# 4port_driver.net
KiCad netlist of a schematic drawn in EAGLE
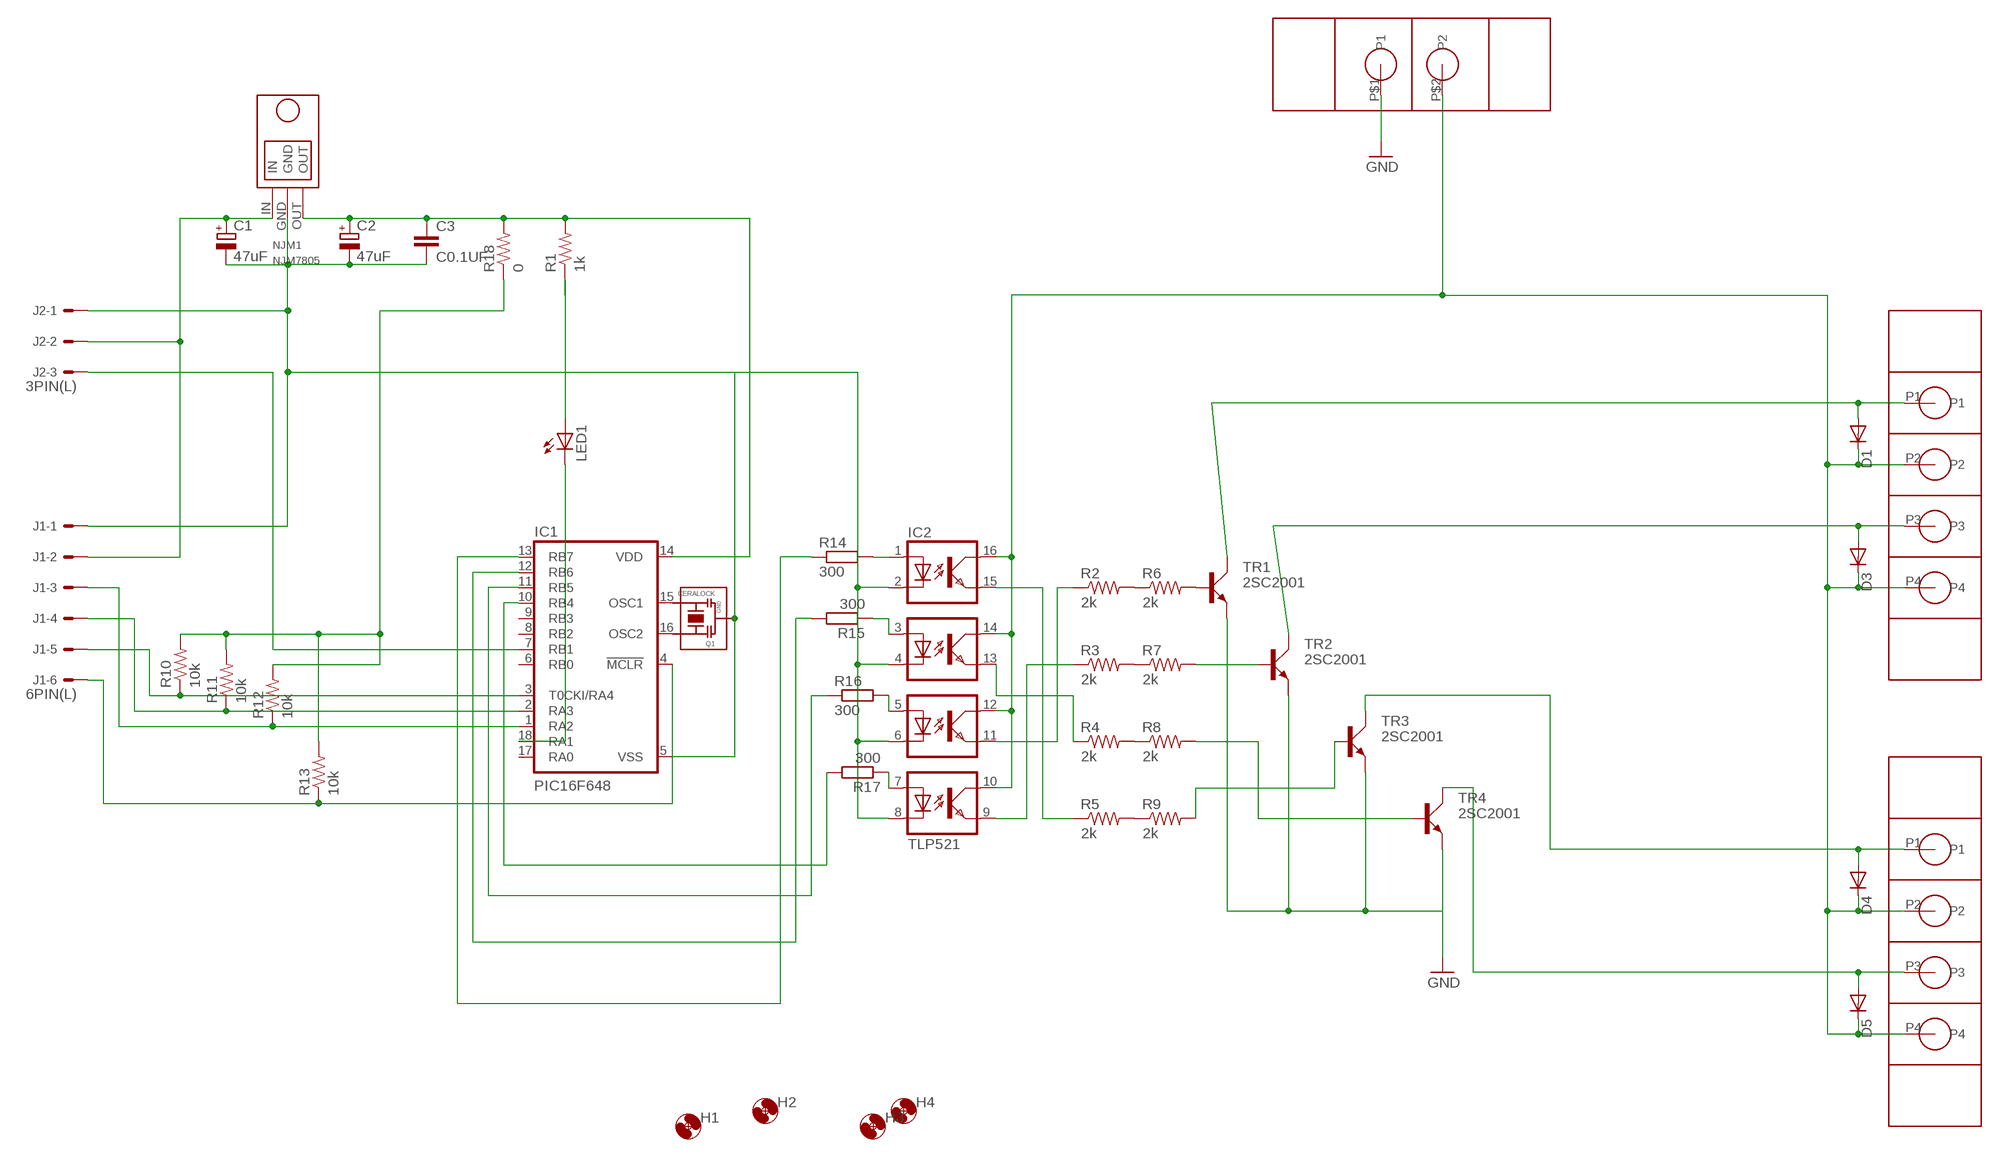
[diagram p0: schematic, sheet 1]

(export (version "E")
  (design (tool "Eeschema 10.0.6"))
  (components
    (comp (ref "C1")
      (value "47uF")
      (footprint "eagle-import:C-6MM")
      (libsource (lib "eagle-import") (part "C-ELEC"))
    )
    (comp (ref "C2")
      (value "47uF")
      (footprint "eagle-import:C-6MM")
      (libsource (lib "eagle-import") (part "C-ELEC"))
    )
    (comp (ref "C3")
      (value "C0.1UF")
      (footprint "eagle-import:C0.1UF")
      (libsource (lib "eagle-import") (part "C0.1UF"))
    )
    (comp (ref "D1")
      (value "DIODE7.5")
      (footprint "eagle-import:DIODE7.5")
      (libsource (lib "eagle-import") (part "DIODE7.5"))
    )
    (comp (ref "D3")
      (value "DIODE7.5")
      (footprint "eagle-import:DIODE7.5")
      (libsource (lib "eagle-import") (part "DIODE7.5"))
    )
    (comp (ref "D4")
      (value "DIODE7.5")
      (footprint "eagle-import:DIODE7.5")
      (libsource (lib "eagle-import") (part "DIODE7.5"))
    )
    (comp (ref "D5")
      (value "DIODE7.5")
      (footprint "eagle-import:DIODE7.5")
      (libsource (lib "eagle-import") (part "DIODE7.5"))
    )
    (comp (ref "H1")
      (value "HOLE3.3M3BOLT")
      (footprint "eagle-import:HOLE3.3")
      (libsource (lib "eagle-import") (part "HOLE3.3M3BOLT"))
    )
    (comp (ref "H2")
      (value "HOLE3.3M3BOLT")
      (footprint "eagle-import:HOLE3.3")
      (libsource (lib "eagle-import") (part "HOLE3.3M3BOLT"))
    )
    (comp (ref "H3")
      (value "HOLE3.3M3BOLT")
      (footprint "eagle-import:HOLE3.3")
      (libsource (lib "eagle-import") (part "HOLE3.3M3BOLT"))
    )
    (comp (ref "H4")
      (value "HOLE3.3M3BOLT")
      (footprint "eagle-import:HOLE3.3")
      (libsource (lib "eagle-import") (part "HOLE3.3M3BOLT"))
    )
    (comp (ref "IC1")
      (value "PIC16F648")
      (footprint "eagle-import:DIL18")
      (libsource (lib "eagle-import") (part "PIC16F648"))
    )
    (comp (ref "IC2")
      (value "TLP521")
      (footprint "eagle-import:DIL16")
      (libsource (lib "eagle-import") (part "TLP521"))
    )
    (comp (ref "J1")
      (value "6PIN(L)")
      (footprint "eagle-import:6PL")
      (libsource (lib "eagle-import") (part "6PIN(L)"))
    )
    (comp (ref "J2")
      (value "3PIN(L)")
      (footprint "eagle-import:3PL")
      (libsource (lib "eagle-import") (part "3PIN(L)"))
    )
    (comp (ref "LED1")
      (value "LED")
      (footprint "eagle-import:LED5MM")
      (libsource (lib "eagle-import") (part "LED"))
    )
    (comp (ref "NJM1")
      (value "NJM7805")
      (footprint "eagle-import:NJM7805")
      (libsource (lib "eagle-import") (part "NJM7805"))
    )
    (comp (ref "Q1")
      (value "CERALOCK")
      (footprint "eagle-import:CERALOCK")
      (libsource (lib "eagle-import") (part "CERALOCK"))
    )
    (comp (ref "R1")
      (value "1k")
      (footprint "eagle-import:0207_10")
      (libsource (lib "eagle-import") (part "R-"))
    )
    (comp (ref "R2")
      (value "2k")
      (footprint "eagle-import:0207_10")
      (libsource (lib "eagle-import") (part "R-"))
    )
    (comp (ref "R3")
      (value "2k")
      (footprint "eagle-import:0207_10")
      (libsource (lib "eagle-import") (part "R-"))
    )
    (comp (ref "R4")
      (value "2k")
      (footprint "eagle-import:0207_10")
      (libsource (lib "eagle-import") (part "R-"))
    )
    (comp (ref "R5")
      (value "2k")
      (footprint "eagle-import:0207_10")
      (libsource (lib "eagle-import") (part "R-"))
    )
    (comp (ref "R6")
      (value "2k")
      (footprint "eagle-import:0207_10")
      (libsource (lib "eagle-import") (part "R-"))
    )
    (comp (ref "R7")
      (value "2k")
      (footprint "eagle-import:0207_10")
      (libsource (lib "eagle-import") (part "R-"))
    )
    (comp (ref "R8")
      (value "2k")
      (footprint "eagle-import:0207_10")
      (libsource (lib "eagle-import") (part "R-"))
    )
    (comp (ref "R9")
      (value "2k")
      (footprint "eagle-import:0207_10")
      (libsource (lib "eagle-import") (part "R-"))
    )
    (comp (ref "R10")
      (value "10k")
      (footprint "eagle-import:0207_10")
      (libsource (lib "eagle-import") (part "R-"))
    )
    (comp (ref "R11")
      (value "10k")
      (footprint "eagle-import:0207_10")
      (libsource (lib "eagle-import") (part "R-"))
    )
    (comp (ref "R12")
      (value "10k")
      (footprint "eagle-import:0207_10")
      (libsource (lib "eagle-import") (part "R-"))
    )
    (comp (ref "R13")
      (value "10k")
      (footprint "eagle-import:0207_10")
      (libsource (lib "eagle-import") (part "R-"))
    )
    (comp (ref "R14")
      (value "300")
      (footprint "eagle-import:R0207V")
      (libsource (lib "eagle-import") (part "R-EU2R0207V"))
    )
    (comp (ref "R15")
      (value "300")
      (footprint "eagle-import:R0207V")
      (libsource (lib "eagle-import") (part "R-EU2R0207V"))
    )
    (comp (ref "R16")
      (value "300")
      (footprint "eagle-import:R0207V")
      (libsource (lib "eagle-import") (part "R-EU2R0207V"))
    )
    (comp (ref "R17")
      (value "300")
      (footprint "eagle-import:R0207V")
      (libsource (lib "eagle-import") (part "R-EU2R0207V"))
    )
    (comp (ref "R18")
      (value "0")
      (footprint "eagle-import:0207_10")
      (libsource (lib "eagle-import") (part "R-"))
    )
    (comp (ref "TR1")
      (value "2SC2001")
      (footprint "eagle-import:TO92BCE")
      (libsource (lib "eagle-import") (part "2SC2001"))
    )
    (comp (ref "TR2")
      (value "2SC2001")
      (footprint "eagle-import:TO92BCE")
      (libsource (lib "eagle-import") (part "2SC2001"))
    )
    (comp (ref "TR3")
      (value "2SC2001")
      (footprint "eagle-import:TO92BCE")
      (libsource (lib "eagle-import") (part "2SC2001"))
    )
    (comp (ref "TR4")
      (value "2SC2001")
      (footprint "eagle-import:TO92BCE")
      (libsource (lib "eagle-import") (part "2SC2001"))
    )
    (comp (ref "U$1")
      (value "BP341L_1")
      (footprint "eagle-import:BP341L")
      (libsource (lib "eagle-import") (part "BP341L_1"))
    )
    (comp (ref "U$2")
      (value "BP341L")
      (footprint "eagle-import:BP341L")
      (libsource (lib "eagle-import") (part "BP341L"))
    )
    (comp (ref "U$3")
      (value "BP341L")
      (footprint "eagle-import:BP341L")
      (libsource (lib "eagle-import") (part "BP341L"))
    )
  )
  (nets
    (net (code "1") (name "GND") (class "Default")
      (node (ref "TR1") (pin "E") (pinfunction "E_E") (pintype "passive"))
      (node (ref "TR2") (pin "E") (pinfunction "E_E") (pintype "passive"))
      (node (ref "TR3") (pin "E") (pinfunction "E_E") (pintype "passive"))
      (node (ref "TR4") (pin "E") (pinfunction "E_E") (pintype "passive"))
      (node (ref "U$1") (pin "P$1") (pinfunction "P1_P$1") (pintype "bidirectional"))
    )
    (net (code "2") (name "Net-(D1-A)") (class "Default")
      (node (ref "D1") (pin "PA") (pinfunction "A_PA") (pintype "passive"))
      (node (ref "TR1") (pin "C") (pinfunction "C_C") (pintype "passive"))
      (node (ref "U$2") (pin "P1") (pinfunction "P1_P1") (pintype "bidirectional"))
    )
    (net (code "3") (name "Net-(D1-C)") (class "Default")
      (node (ref "D1") (pin "PK") (pinfunction "C_PK") (pintype "passive"))
      (node (ref "D3") (pin "PK") (pinfunction "C_PK") (pintype "passive"))
      (node (ref "D4") (pin "PK") (pinfunction "C_PK") (pintype "passive"))
      (node (ref "D5") (pin "PK") (pinfunction "C_PK") (pintype "passive"))
      (node (ref "IC2") (pin "10") (pinfunction "COL3_10") (pintype "passive"))
      (node (ref "IC2") (pin "12") (pinfunction "COL2_12") (pintype "passive"))
      (node (ref "IC2") (pin "14") (pinfunction "COL1_14") (pintype "passive"))
      (node (ref "IC2") (pin "16") (pinfunction "COL0_16") (pintype "passive"))
      (node (ref "U$1") (pin "P$2") (pinfunction "P2_P$2") (pintype "bidirectional"))
      (node (ref "U$2") (pin "P2") (pinfunction "P2_P2") (pintype "bidirectional"))
      (node (ref "U$2") (pin "P4") (pinfunction "P4_P4") (pintype "bidirectional"))
      (node (ref "U$3") (pin "P2") (pinfunction "P2_P2") (pintype "bidirectional"))
      (node (ref "U$3") (pin "P4") (pinfunction "P4_P4") (pintype "bidirectional"))
    )
    (net (code "4") (name "Net-(D3-A)") (class "Default")
      (node (ref "D3") (pin "PA") (pinfunction "A_PA") (pintype "passive"))
      (node (ref "TR2") (pin "C") (pinfunction "C_C") (pintype "passive"))
      (node (ref "U$2") (pin "P3") (pinfunction "P3_P3") (pintype "bidirectional"))
    )
    (net (code "5") (name "Net-(D4-A)") (class "Default")
      (node (ref "D4") (pin "PA") (pinfunction "A_PA") (pintype "passive"))
      (node (ref "TR3") (pin "C") (pinfunction "C_C") (pintype "passive"))
      (node (ref "U$3") (pin "P1") (pinfunction "P1_P1") (pintype "bidirectional"))
    )
    (net (code "6") (name "Net-(D5-A)") (class "Default")
      (node (ref "D5") (pin "PA") (pinfunction "A_PA") (pintype "passive"))
      (node (ref "TR4") (pin "C") (pinfunction "C_C") (pintype "passive"))
      (node (ref "U$3") (pin "P3") (pinfunction "P3_P3") (pintype "bidirectional"))
    )
    (net (code "7") (name "Net-(IC1-OSC1)") (class "Default")
      (node (ref "IC1") (pin "15") (pinfunction "OSC1_15") (pintype "input"))
      (node (ref "Q1") (pin "P$3") (pinfunction "P$3_P$3") (pintype "passive"))
    )
    (net (code "8") (name "Net-(IC1-OSC2)") (class "Default")
      (node (ref "IC1") (pin "16") (pinfunction "OSC2_16") (pintype "output"))
      (node (ref "Q1") (pin "P$1") (pinfunction "P$1_P$1") (pintype "passive"))
    )
    (net (code "9") (name "Net-(IC1-RA1)") (class "Default")
      (node (ref "IC1") (pin "18") (pinfunction "RA1_18") (pintype "bidirectional"))
      (node (ref "LED1") (pin "K") (pinfunction "C_K") (pintype "passive"))
    )
    (net (code "10") (name "Net-(IC1-RA2)") (class "Default")
      (node (ref "IC1") (pin "1") (pinfunction "RA2_1") (pintype "bidirectional"))
      (node (ref "J1") (pin "3") (pinfunction "S_3") (pintype "passive"))
      (node (ref "R12") (pin "1") (pinfunction "1_1") (pintype "passive"))
    )
    (net (code "11") (name "Net-(IC1-RA3)") (class "Default")
      (node (ref "IC1") (pin "2") (pinfunction "RA3_2") (pintype "bidirectional"))
      (node (ref "J1") (pin "4") (pinfunction "S_4") (pintype "passive"))
      (node (ref "R11") (pin "1") (pinfunction "1_1") (pintype "passive"))
    )
    (net (code "12") (name "Net-(IC1-RB1)") (class "Default")
      (node (ref "IC1") (pin "7") (pinfunction "RB1_7") (pintype "bidirectional"))
      (node (ref "J2") (pin "3") (pinfunction "S_3") (pintype "passive"))
    )
    (net (code "13") (name "Net-(IC1-RB4)") (class "Default")
      (node (ref "IC1") (pin "10") (pinfunction "RB4_10") (pintype "bidirectional"))
      (node (ref "R17") (pin "2") (pinfunction "2_2") (pintype "passive"))
    )
    (net (code "14") (name "Net-(IC1-RB5)") (class "Default")
      (node (ref "IC1") (pin "11") (pinfunction "RB5_11") (pintype "bidirectional"))
      (node (ref "R16") (pin "1") (pinfunction "1_1") (pintype "passive"))
    )
    (net (code "15") (name "Net-(IC1-RB6)") (class "Default")
      (node (ref "IC1") (pin "12") (pinfunction "RB6_12") (pintype "bidirectional"))
      (node (ref "R15") (pin "2") (pinfunction "2_2") (pintype "passive"))
    )
    (net (code "16") (name "Net-(IC1-RB7)") (class "Default")
      (node (ref "IC1") (pin "13") (pinfunction "RB7_13") (pintype "bidirectional"))
      (node (ref "R14") (pin "1") (pinfunction "1_1") (pintype "passive"))
    )
    (net (code "17") (name "Net-(IC1-T0CKI{slash}RA4)") (class "Default")
      (node (ref "IC1") (pin "3") (pinfunction "T0CKI/RA4_3") (pintype "bidirectional"))
      (node (ref "J1") (pin "5") (pinfunction "S_5") (pintype "passive"))
      (node (ref "R10") (pin "1") (pinfunction "1_1") (pintype "passive"))
    )
    (net (code "18") (name "Net-(IC1-VDD)") (class "Default")
      (node (ref "C2") (pin "+") (pinfunction "+_+") (pintype "passive"))
      (node (ref "C3") (pin "1") (pinfunction "1_1") (pintype "passive"))
      (node (ref "IC1") (pin "14") (pinfunction "VDD_14") (pintype "power_in"))
      (node (ref "NJM1") (pin "OUT") (pinfunction "OUT_OUT") (pintype "bidirectional"))
      (node (ref "R1") (pin "2") (pinfunction "2_2") (pintype "passive"))
      (node (ref "R18") (pin "2") (pinfunction "2_2") (pintype "passive"))
    )
    (net (code "19") (name "Net-(IC1-VSS)") (class "Default")
      (node (ref "C1") (pin "-") (pinfunction "-_-") (pintype "passive"))
      (node (ref "C2") (pin "-") (pinfunction "-_-") (pintype "passive"))
      (node (ref "C3") (pin "2") (pinfunction "2_2") (pintype "passive"))
      (node (ref "IC1") (pin "5") (pinfunction "VSS_5") (pintype "power_in"))
      (node (ref "IC2") (pin "2") (pinfunction "C0_2") (pintype "passive"))
      (node (ref "IC2") (pin "4") (pinfunction "C1_4") (pintype "passive"))
      (node (ref "IC2") (pin "6") (pinfunction "C2_6") (pintype "passive"))
      (node (ref "IC2") (pin "8") (pinfunction "C3_8") (pintype "passive"))
      (node (ref "J1") (pin "1") (pinfunction "S_1") (pintype "passive"))
      (node (ref "J2") (pin "1") (pinfunction "S_1") (pintype "passive"))
      (node (ref "NJM1") (pin "GND") (pinfunction "GND_GND") (pintype "bidirectional"))
      (node (ref "Q1") (pin "P$2") (pinfunction "P$2_P$2") (pintype "passive"))
    )
    (net (code "20") (name "Net-(IC1-~{MCLR})") (class "Default")
      (node (ref "IC1") (pin "4") (pinfunction "~{MCLR}_4") (pintype "input"))
      (node (ref "J1") (pin "6") (pinfunction "S_6") (pintype "passive"))
      (node (ref "R13") (pin "1") (pinfunction "1_1") (pintype "passive"))
    )
    (net (code "21") (name "Net-(IC2-A0)") (class "Default")
      (node (ref "IC2") (pin "1") (pinfunction "A0_1") (pintype "passive"))
      (node (ref "R14") (pin "2") (pinfunction "2_2") (pintype "passive"))
    )
    (net (code "22") (name "Net-(IC2-A1)") (class "Default")
      (node (ref "IC2") (pin "3") (pinfunction "A1_3") (pintype "passive"))
      (node (ref "R15") (pin "1") (pinfunction "1_1") (pintype "passive"))
    )
    (net (code "23") (name "Net-(IC2-A2)") (class "Default")
      (node (ref "IC2") (pin "5") (pinfunction "A2_5") (pintype "passive"))
      (node (ref "R16") (pin "2") (pinfunction "2_2") (pintype "passive"))
    )
    (net (code "24") (name "Net-(IC2-A3)") (class "Default")
      (node (ref "IC2") (pin "7") (pinfunction "A3_7") (pintype "passive"))
      (node (ref "R17") (pin "1") (pinfunction "1_1") (pintype "passive"))
    )
    (net (code "25") (name "Net-(IC2-EMIT0)") (class "Default")
      (node (ref "IC2") (pin "15") (pinfunction "EMIT0_15") (pintype "passive"))
      (node (ref "R5") (pin "1") (pinfunction "1_1") (pintype "passive"))
    )
    (net (code "26") (name "Net-(IC2-EMIT1)") (class "Default")
      (node (ref "IC2") (pin "13") (pinfunction "EMIT1_13") (pintype "passive"))
      (node (ref "R4") (pin "1") (pinfunction "1_1") (pintype "passive"))
    )
    (net (code "27") (name "Net-(IC2-EMIT2)") (class "Default")
      (node (ref "IC2") (pin "11") (pinfunction "EMIT2_11") (pintype "passive"))
      (node (ref "R2") (pin "1") (pinfunction "1_1") (pintype "passive"))
    )
    (net (code "28") (name "Net-(IC2-EMIT3)") (class "Default")
      (node (ref "IC2") (pin "9") (pinfunction "EMIT3_9") (pintype "passive"))
      (node (ref "R3") (pin "1") (pinfunction "1_1") (pintype "passive"))
    )
    (net (code "29") (name "Net-(J1B-S)") (class "Default")
      (node (ref "C1") (pin "+") (pinfunction "+_+") (pintype "passive"))
      (node (ref "J1") (pin "2") (pinfunction "S_2") (pintype "passive"))
      (node (ref "J2") (pin "2") (pinfunction "S_2") (pintype "passive"))
      (node (ref "NJM1") (pin "IN") (pinfunction "IN_IN") (pintype "bidirectional"))
    )
    (net (code "30") (name "Net-(LED1-PadA)") (class "Default")
      (node (ref "LED1") (pin "A") (pinfunction "A_A") (pintype "passive"))
      (node (ref "R1") (pin "1") (pinfunction "1_1") (pintype "passive"))
    )
    (net (code "31") (name "Net-(R2-Pad2)") (class "Default")
      (node (ref "R2") (pin "2") (pinfunction "2_2") (pintype "passive"))
      (node (ref "R6") (pin "1") (pinfunction "1_1") (pintype "passive"))
    )
    (net (code "32") (name "Net-(R3-Pad2)") (class "Default")
      (node (ref "R3") (pin "2") (pinfunction "2_2") (pintype "passive"))
      (node (ref "R7") (pin "1") (pinfunction "1_1") (pintype "passive"))
    )
    (net (code "33") (name "Net-(R4-Pad2)") (class "Default")
      (node (ref "R4") (pin "2") (pinfunction "2_2") (pintype "passive"))
      (node (ref "R8") (pin "1") (pinfunction "1_1") (pintype "passive"))
    )
    (net (code "34") (name "Net-(R5-Pad2)") (class "Default")
      (node (ref "R5") (pin "2") (pinfunction "2_2") (pintype "passive"))
      (node (ref "R9") (pin "1") (pinfunction "1_1") (pintype "passive"))
    )
    (net (code "35") (name "Net-(R6-Pad2)") (class "Default")
      (node (ref "R6") (pin "2") (pinfunction "2_2") (pintype "passive"))
      (node (ref "TR1") (pin "B") (pinfunction "B_B") (pintype "passive"))
    )
    (net (code "36") (name "Net-(R7-Pad2)") (class "Default")
      (node (ref "R7") (pin "2") (pinfunction "2_2") (pintype "passive"))
      (node (ref "TR2") (pin "B") (pinfunction "B_B") (pintype "passive"))
    )
    (net (code "37") (name "Net-(R8-Pad2)") (class "Default")
      (node (ref "R8") (pin "2") (pinfunction "2_2") (pintype "passive"))
      (node (ref "TR4") (pin "B") (pinfunction "B_B") (pintype "passive"))
    )
    (net (code "38") (name "Net-(R9-Pad2)") (class "Default")
      (node (ref "R9") (pin "2") (pinfunction "2_2") (pintype "passive"))
      (node (ref "TR3") (pin "B") (pinfunction "B_B") (pintype "passive"))
    )
    (net (code "39") (name "Net-(R10-Pad2)") (class "Default")
      (node (ref "R10") (pin "2") (pinfunction "2_2") (pintype "passive"))
      (node (ref "R11") (pin "2") (pinfunction "2_2") (pintype "passive"))
      (node (ref "R12") (pin "2") (pinfunction "2_2") (pintype "passive"))
      (node (ref "R13") (pin "2") (pinfunction "2_2") (pintype "passive"))
      (node (ref "R18") (pin "1") (pinfunction "1_1") (pintype "passive"))
    )
    (net (code "40") (name "unconnected-(IC1-RA0-Pad17)") (class "Default")
      (node (ref "IC1") (pin "17") (pinfunction "RA0_17") (pintype "bidirectional"))
    )
    (net (code "41") (name "unconnected-(IC1-RB0-Pad6)") (class "Default")
      (node (ref "IC1") (pin "6") (pinfunction "RB0_6") (pintype "bidirectional"))
    )
    (net (code "42") (name "unconnected-(IC1-RB2-Pad8)") (class "Default")
      (node (ref "IC1") (pin "8") (pinfunction "RB2_8") (pintype "bidirectional"))
    )
    (net (code "43") (name "unconnected-(IC1-RB3-Pad9)") (class "Default")
      (node (ref "IC1") (pin "9") (pinfunction "RB3_9") (pintype "bidirectional"))
    )
  )
)
